# ADC.net
KiCad netlist of a schematic drawn in Altium Designer
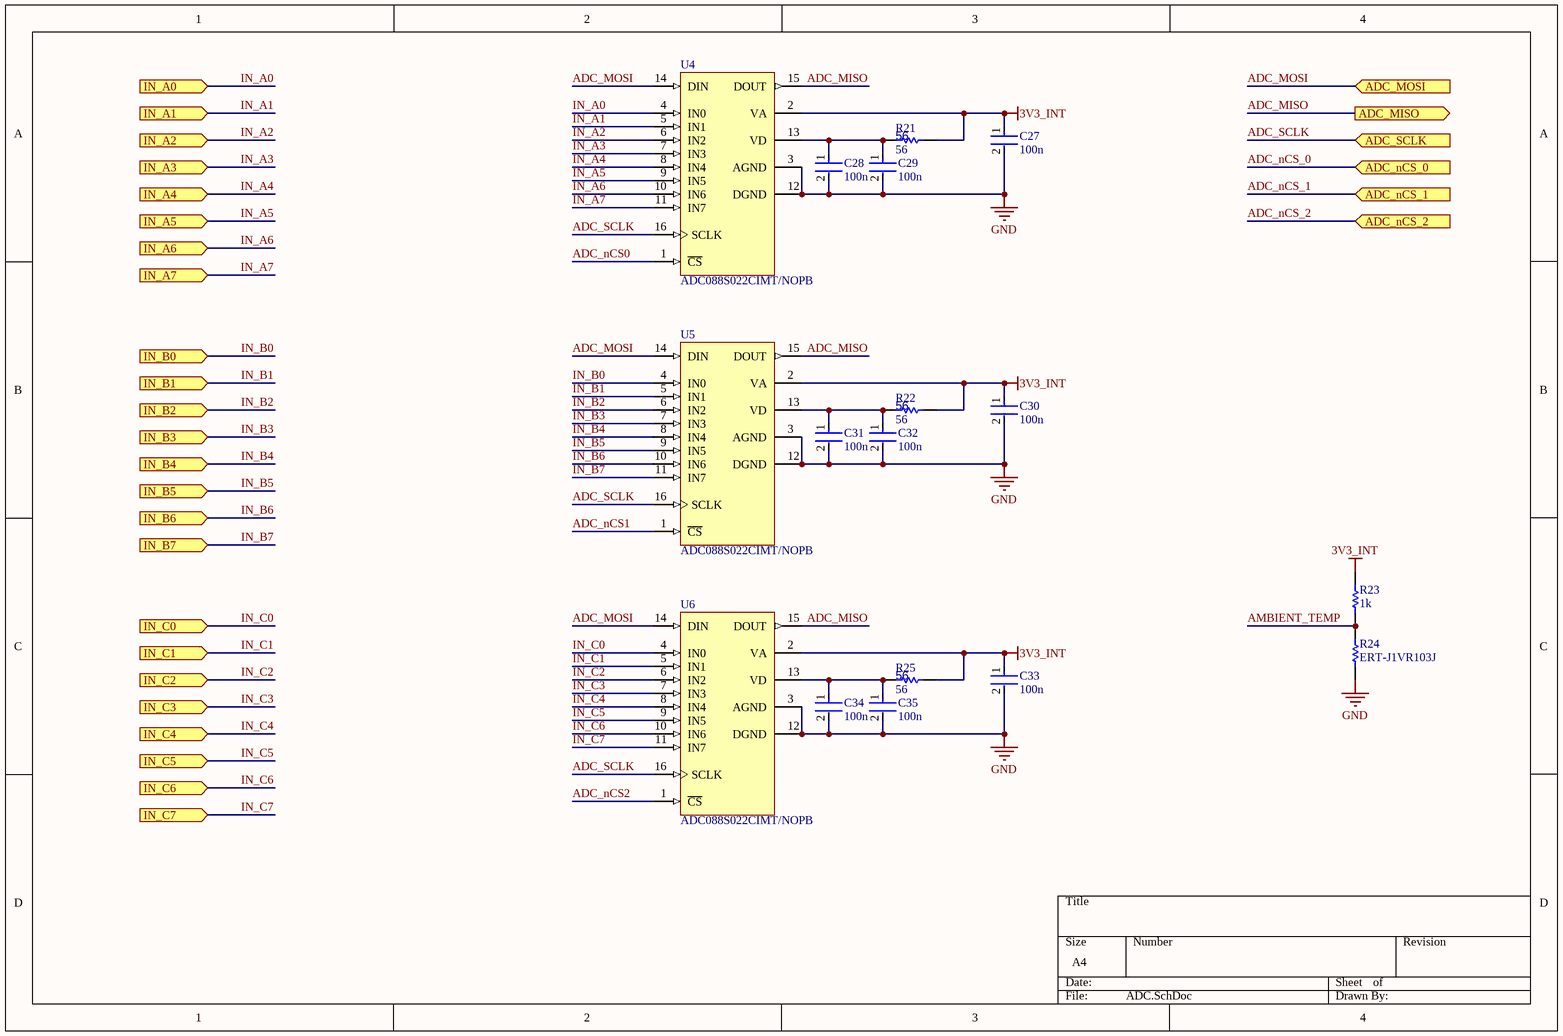
[diagram p0: ADC.SchDoc]

(export (version "E")
  (design (tool "Eeschema 10.0.6"))
  (components
    (comp (ref "C27")
      (value "100n")
      (footprint "FP-0402-L_1_0_0_05-W_0_5-IPC_A")
      (description "LARGE PADS, 0402 CAP, CHANGE COMMENT TO MATCH REAL P/N")
      (libsource (lib "Space Concordia") (part "b4654b650e69147ec39a6b967a45e02"))
    )
    (comp (ref "C28")
      (value "100n")
      (footprint "FP-0402-L_1_0_0_05-W_0_5-IPC_A")
      (description "LARGE PADS, 0402 CAP, CHANGE COMMENT TO MATCH REAL P/N")
      (libsource (lib "Space Concordia") (part "b4654b650e69147ec39a6b967a45e02"))
    )
    (comp (ref "C29")
      (value "100n")
      (footprint "FP-0402-L_1_0_0_05-W_0_5-IPC_A")
      (description "LARGE PADS, 0402 CAP, CHANGE COMMENT TO MATCH REAL P/N")
      (libsource (lib "Space Concordia") (part "b4654b650e69147ec39a6b967a45e02"))
    )
    (comp (ref "C30")
      (value "100n")
      (footprint "FP-0402-L_1_0_0_05-W_0_5-IPC_A")
      (description "LARGE PADS, 0402 CAP, CHANGE COMMENT TO MATCH REAL P/N")
      (libsource (lib "Space Concordia") (part "b4654b650e69147ec39a6b967a45e02"))
    )
    (comp (ref "C31")
      (value "100n")
      (footprint "FP-0402-L_1_0_0_05-W_0_5-IPC_A")
      (description "LARGE PADS, 0402 CAP, CHANGE COMMENT TO MATCH REAL P/N")
      (libsource (lib "Space Concordia") (part "b4654b650e69147ec39a6b967a45e02"))
    )
    (comp (ref "C32")
      (value "100n")
      (footprint "FP-0402-L_1_0_0_05-W_0_5-IPC_A")
      (description "LARGE PADS, 0402 CAP, CHANGE COMMENT TO MATCH REAL P/N")
      (libsource (lib "Space Concordia") (part "b4654b650e69147ec39a6b967a45e02"))
    )
    (comp (ref "C33")
      (value "100n")
      (footprint "FP-0402-L_1_0_0_05-W_0_5-IPC_A")
      (description "LARGE PADS, 0402 CAP, CHANGE COMMENT TO MATCH REAL P/N")
      (libsource (lib "Space Concordia") (part "b4654b650e69147ec39a6b967a45e02"))
    )
    (comp (ref "C34")
      (value "100n")
      (footprint "FP-0402-L_1_0_0_05-W_0_5-IPC_A")
      (description "LARGE PADS, 0402 CAP, CHANGE COMMENT TO MATCH REAL P/N")
      (libsource (lib "Space Concordia") (part "b4654b650e69147ec39a6b967a45e02"))
    )
    (comp (ref "C35")
      (value "100n")
      (footprint "FP-0402-L_1_0_0_05-W_0_5-IPC_A")
      (description "LARGE PADS, 0402 CAP, CHANGE COMMENT TO MATCH REAL P/N")
      (libsource (lib "Space Concordia") (part "b4654b650e69147ec39a6b967a45e02"))
    )
    (comp (ref "R21")
      (value "56")
      (footprint "R0603B")
      (description "Resistor")
      (fields (field (name "ALTIUM_VALUE") "56"))
      (libsource (lib "Space Concordia") (part "Resistor"))
    )
    (comp (ref "R22")
      (value "56")
      (footprint "R0603B")
      (description "Resistor")
      (fields (field (name "ALTIUM_VALUE") "56"))
      (libsource (lib "Space Concordia") (part "Resistor"))
    )
    (comp (ref "R23")
      (value "1k")
      (footprint "R0603B")
      (description "Resistor")
      (libsource (lib "Space Concordia") (part "Resistor"))
    )
    (comp (ref "R24")
      (value "ERT-J1VR103J")
      (footprint "RESC1608X90X30ML15T20")
      (fields (field (name "MANUFACTURER") "Panasonic"))
      (libsource (lib "Altium Content Vault") (part "RES"))
    )
    (comp (ref "R25")
      (value "56")
      (footprint "R0603B")
      (description "Resistor")
      (fields (field (name "ALTIUM_VALUE") "56"))
      (libsource (lib "Space Concordia") (part "Resistor"))
    )
    (comp (ref "U4")
      (value "ADC088S022CIMT/NOPB")
      (footprint "MTC16_L")
      (description "8-Channel, 50 kSPS to 200 kSPS, 8-Bit A/D Converter, 16-pin TSSOP, Pb-Free")
      (fields (field (name "MANUFACTURER") "National Semiconductor"))
      (libsource (lib "Altium Content Vault") (part "CON-ADC-ADC108S052CIMT"))
    )
    (comp (ref "U5")
      (value "ADC088S022CIMT/NOPB")
      (footprint "MTC16_L")
      (description "8-Channel, 50 kSPS to 200 kSPS, 8-Bit A/D Converter, 16-pin TSSOP, Pb-Free")
      (fields (field (name "MANUFACTURER") "National Semiconductor"))
      (libsource (lib "Altium Content Vault") (part "CON-ADC-ADC108S052CIMT"))
    )
    (comp (ref "U6")
      (value "ADC088S022CIMT/NOPB")
      (footprint "MTC16_L")
      (description "8-Channel, 50 kSPS to 200 kSPS, 8-Bit A/D Converter, 16-pin TSSOP, Pb-Free")
      (fields (field (name "MANUFACTURER") "National Semiconductor"))
      (libsource (lib "Altium Content Vault") (part "CON-ADC-ADC108S052CIMT"))
    )
  )
  (nets
    (net (code "1") (name "/ADC_MISO") (class "Default")
      (node (ref "U4") (pin "15") (pinfunction "DOUT_15") (pintype "output"))
      (node (ref "U5") (pin "15") (pinfunction "DOUT_15") (pintype "output"))
      (node (ref "U6") (pin "15") (pinfunction "DOUT_15") (pintype "output"))
    )
    (net (code "2") (name "/ADC_MOSI") (class "Default")
      (node (ref "U4") (pin "14") (pinfunction "DIN_14") (pintype "input"))
      (node (ref "U5") (pin "14") (pinfunction "DIN_14") (pintype "input"))
      (node (ref "U6") (pin "14") (pinfunction "DIN_14") (pintype "input"))
    )
    (net (code "3") (name "/ADC_SCLK") (class "Default")
      (node (ref "U4") (pin "16") (pinfunction "SCLK_16") (pintype "input"))
      (node (ref "U5") (pin "16") (pinfunction "SCLK_16") (pintype "input"))
      (node (ref "U6") (pin "16") (pinfunction "SCLK_16") (pintype "input"))
    )
    (net (code "4") (name "/ADC_nCS0") (class "Default")
      (node (ref "U4") (pin "1") (pinfunction "~{CS}_1") (pintype "input"))
    )
    (net (code "5") (name "/ADC_nCS1") (class "Default")
      (node (ref "U5") (pin "1") (pinfunction "~{CS}_1") (pintype "input"))
    )
    (net (code "6") (name "/ADC_nCS2") (class "Default")
      (node (ref "U6") (pin "1") (pinfunction "~{CS}_1") (pintype "input"))
    )
    (net (code "10") (name "/AMBIENT_TEMP") (class "Default")
      (node (ref "R23") (pin "1") (pinfunction "1_1") (pintype "passive"))
      (node (ref "R24") (pin "2") (pinfunction "2_2") (pintype "passive"))
    )
    (net (code "11") (name "/IN_A0") (class "Default")
      (node (ref "U4") (pin "4") (pinfunction "IN0_4") (pintype "input"))
    )
    (net (code "12") (name "/IN_A1") (class "Default")
      (node (ref "U4") (pin "5") (pinfunction "IN1_5") (pintype "input"))
    )
    (net (code "13") (name "/IN_A2") (class "Default")
      (node (ref "U4") (pin "6") (pinfunction "IN2_6") (pintype "input"))
    )
    (net (code "14") (name "/IN_A3") (class "Default")
      (node (ref "U4") (pin "7") (pinfunction "IN3_7") (pintype "input"))
    )
    (net (code "15") (name "/IN_A4") (class "Default")
      (node (ref "U4") (pin "8") (pinfunction "IN4_8") (pintype "input"))
    )
    (net (code "16") (name "/IN_A5") (class "Default")
      (node (ref "U4") (pin "9") (pinfunction "IN5_9") (pintype "input"))
    )
    (net (code "17") (name "/IN_A6") (class "Default")
      (node (ref "U4") (pin "10") (pinfunction "IN6_10") (pintype "input"))
    )
    (net (code "18") (name "/IN_A7") (class "Default")
      (node (ref "U4") (pin "11") (pinfunction "IN7_11") (pintype "input"))
    )
    (net (code "19") (name "/IN_B0") (class "Default")
      (node (ref "U5") (pin "4") (pinfunction "IN0_4") (pintype "input"))
    )
    (net (code "20") (name "/IN_B1") (class "Default")
      (node (ref "U5") (pin "5") (pinfunction "IN1_5") (pintype "input"))
    )
    (net (code "21") (name "/IN_B2") (class "Default")
      (node (ref "U5") (pin "6") (pinfunction "IN2_6") (pintype "input"))
    )
    (net (code "22") (name "/IN_B3") (class "Default")
      (node (ref "U5") (pin "7") (pinfunction "IN3_7") (pintype "input"))
    )
    (net (code "23") (name "/IN_B4") (class "Default")
      (node (ref "U5") (pin "8") (pinfunction "IN4_8") (pintype "input"))
    )
    (net (code "24") (name "/IN_B5") (class "Default")
      (node (ref "U5") (pin "9") (pinfunction "IN5_9") (pintype "input"))
    )
    (net (code "25") (name "/IN_B6") (class "Default")
      (node (ref "U5") (pin "10") (pinfunction "IN6_10") (pintype "input"))
    )
    (net (code "26") (name "/IN_B7") (class "Default")
      (node (ref "U5") (pin "11") (pinfunction "IN7_11") (pintype "input"))
    )
    (net (code "27") (name "/IN_C0") (class "Default")
      (node (ref "U6") (pin "4") (pinfunction "IN0_4") (pintype "input"))
    )
    (net (code "28") (name "/IN_C1") (class "Default")
      (node (ref "U6") (pin "5") (pinfunction "IN1_5") (pintype "input"))
    )
    (net (code "29") (name "/IN_C2") (class "Default")
      (node (ref "U6") (pin "6") (pinfunction "IN2_6") (pintype "input"))
    )
    (net (code "30") (name "/IN_C3") (class "Default")
      (node (ref "U6") (pin "7") (pinfunction "IN3_7") (pintype "input"))
    )
    (net (code "31") (name "/IN_C4") (class "Default")
      (node (ref "U6") (pin "8") (pinfunction "IN4_8") (pintype "input"))
    )
    (net (code "32") (name "/IN_C5") (class "Default")
      (node (ref "U6") (pin "9") (pinfunction "IN5_9") (pintype "input"))
    )
    (net (code "33") (name "/IN_C6") (class "Default")
      (node (ref "U6") (pin "10") (pinfunction "IN6_10") (pintype "input"))
    )
    (net (code "34") (name "/IN_C7") (class "Default")
      (node (ref "U6") (pin "11") (pinfunction "IN7_11") (pintype "input"))
    )
    (net (code "35") (name "3V3_INT") (class "Default")
      (node (ref "C27") (pin "1") (pinfunction "1_1") (pintype "passive"))
      (node (ref "C30") (pin "1") (pinfunction "1_1") (pintype "passive"))
      (node (ref "C33") (pin "1") (pinfunction "1_1") (pintype "passive"))
      (node (ref "R21") (pin "1") (pinfunction "1_1") (pintype "passive"))
      (node (ref "R22") (pin "1") (pinfunction "1_1") (pintype "passive"))
      (node (ref "R23") (pin "2") (pinfunction "2_2") (pintype "passive"))
      (node (ref "R25") (pin "1") (pinfunction "1_1") (pintype "passive"))
      (node (ref "U4") (pin "2") (pinfunction "VA_2") (pintype "power_in"))
      (node (ref "U5") (pin "2") (pinfunction "VA_2") (pintype "power_in"))
      (node (ref "U6") (pin "2") (pinfunction "VA_2") (pintype "power_in"))
    )
    (net (code "36") (name "GND") (class "Default")
      (node (ref "C27") (pin "2") (pinfunction "2_2") (pintype "passive"))
      (node (ref "C28") (pin "2") (pinfunction "2_2") (pintype "passive"))
      (node (ref "C29") (pin "2") (pinfunction "2_2") (pintype "passive"))
      (node (ref "C30") (pin "2") (pinfunction "2_2") (pintype "passive"))
      (node (ref "C31") (pin "2") (pinfunction "2_2") (pintype "passive"))
      (node (ref "C32") (pin "2") (pinfunction "2_2") (pintype "passive"))
      (node (ref "C33") (pin "2") (pinfunction "2_2") (pintype "passive"))
      (node (ref "C34") (pin "2") (pinfunction "2_2") (pintype "passive"))
      (node (ref "C35") (pin "2") (pinfunction "2_2") (pintype "passive"))
      (node (ref "R24") (pin "1") (pinfunction "1_1") (pintype "passive"))
      (node (ref "U4") (pin "12") (pinfunction "DGND_12") (pintype "power_in"))
      (node (ref "U4") (pin "3") (pinfunction "AGND_3") (pintype "power_in"))
      (node (ref "U5") (pin "12") (pinfunction "DGND_12") (pintype "power_in"))
      (node (ref "U5") (pin "3") (pinfunction "AGND_3") (pintype "power_in"))
      (node (ref "U6") (pin "12") (pinfunction "DGND_12") (pintype "power_in"))
      (node (ref "U6") (pin "3") (pinfunction "AGND_3") (pintype "power_in"))
    )
    (net (code "37") (name "Net-(U4-VD)") (class "Default")
      (node (ref "C28") (pin "1") (pinfunction "1_1") (pintype "passive"))
      (node (ref "C29") (pin "1") (pinfunction "1_1") (pintype "passive"))
      (node (ref "R21") (pin "2") (pinfunction "2_2") (pintype "passive"))
      (node (ref "U4") (pin "13") (pinfunction "VD_13") (pintype "power_in"))
    )
    (net (code "38") (name "Net-(U5-VD)") (class "Default")
      (node (ref "C31") (pin "1") (pinfunction "1_1") (pintype "passive"))
      (node (ref "C32") (pin "1") (pinfunction "1_1") (pintype "passive"))
      (node (ref "R22") (pin "2") (pinfunction "2_2") (pintype "passive"))
      (node (ref "U5") (pin "13") (pinfunction "VD_13") (pintype "power_in"))
    )
    (net (code "39") (name "Net-(U6-VD)") (class "Default")
      (node (ref "C34") (pin "1") (pinfunction "1_1") (pintype "passive"))
      (node (ref "C35") (pin "1") (pinfunction "1_1") (pintype "passive"))
      (node (ref "R25") (pin "2") (pinfunction "2_2") (pintype "passive"))
      (node (ref "U6") (pin "13") (pinfunction "VD_13") (pintype "power_in"))
    )
  )
)
